# espnative-deadrail-2-g-rendered-poly-via.net
KiCad netlist of a schematic drawn in EAGLE
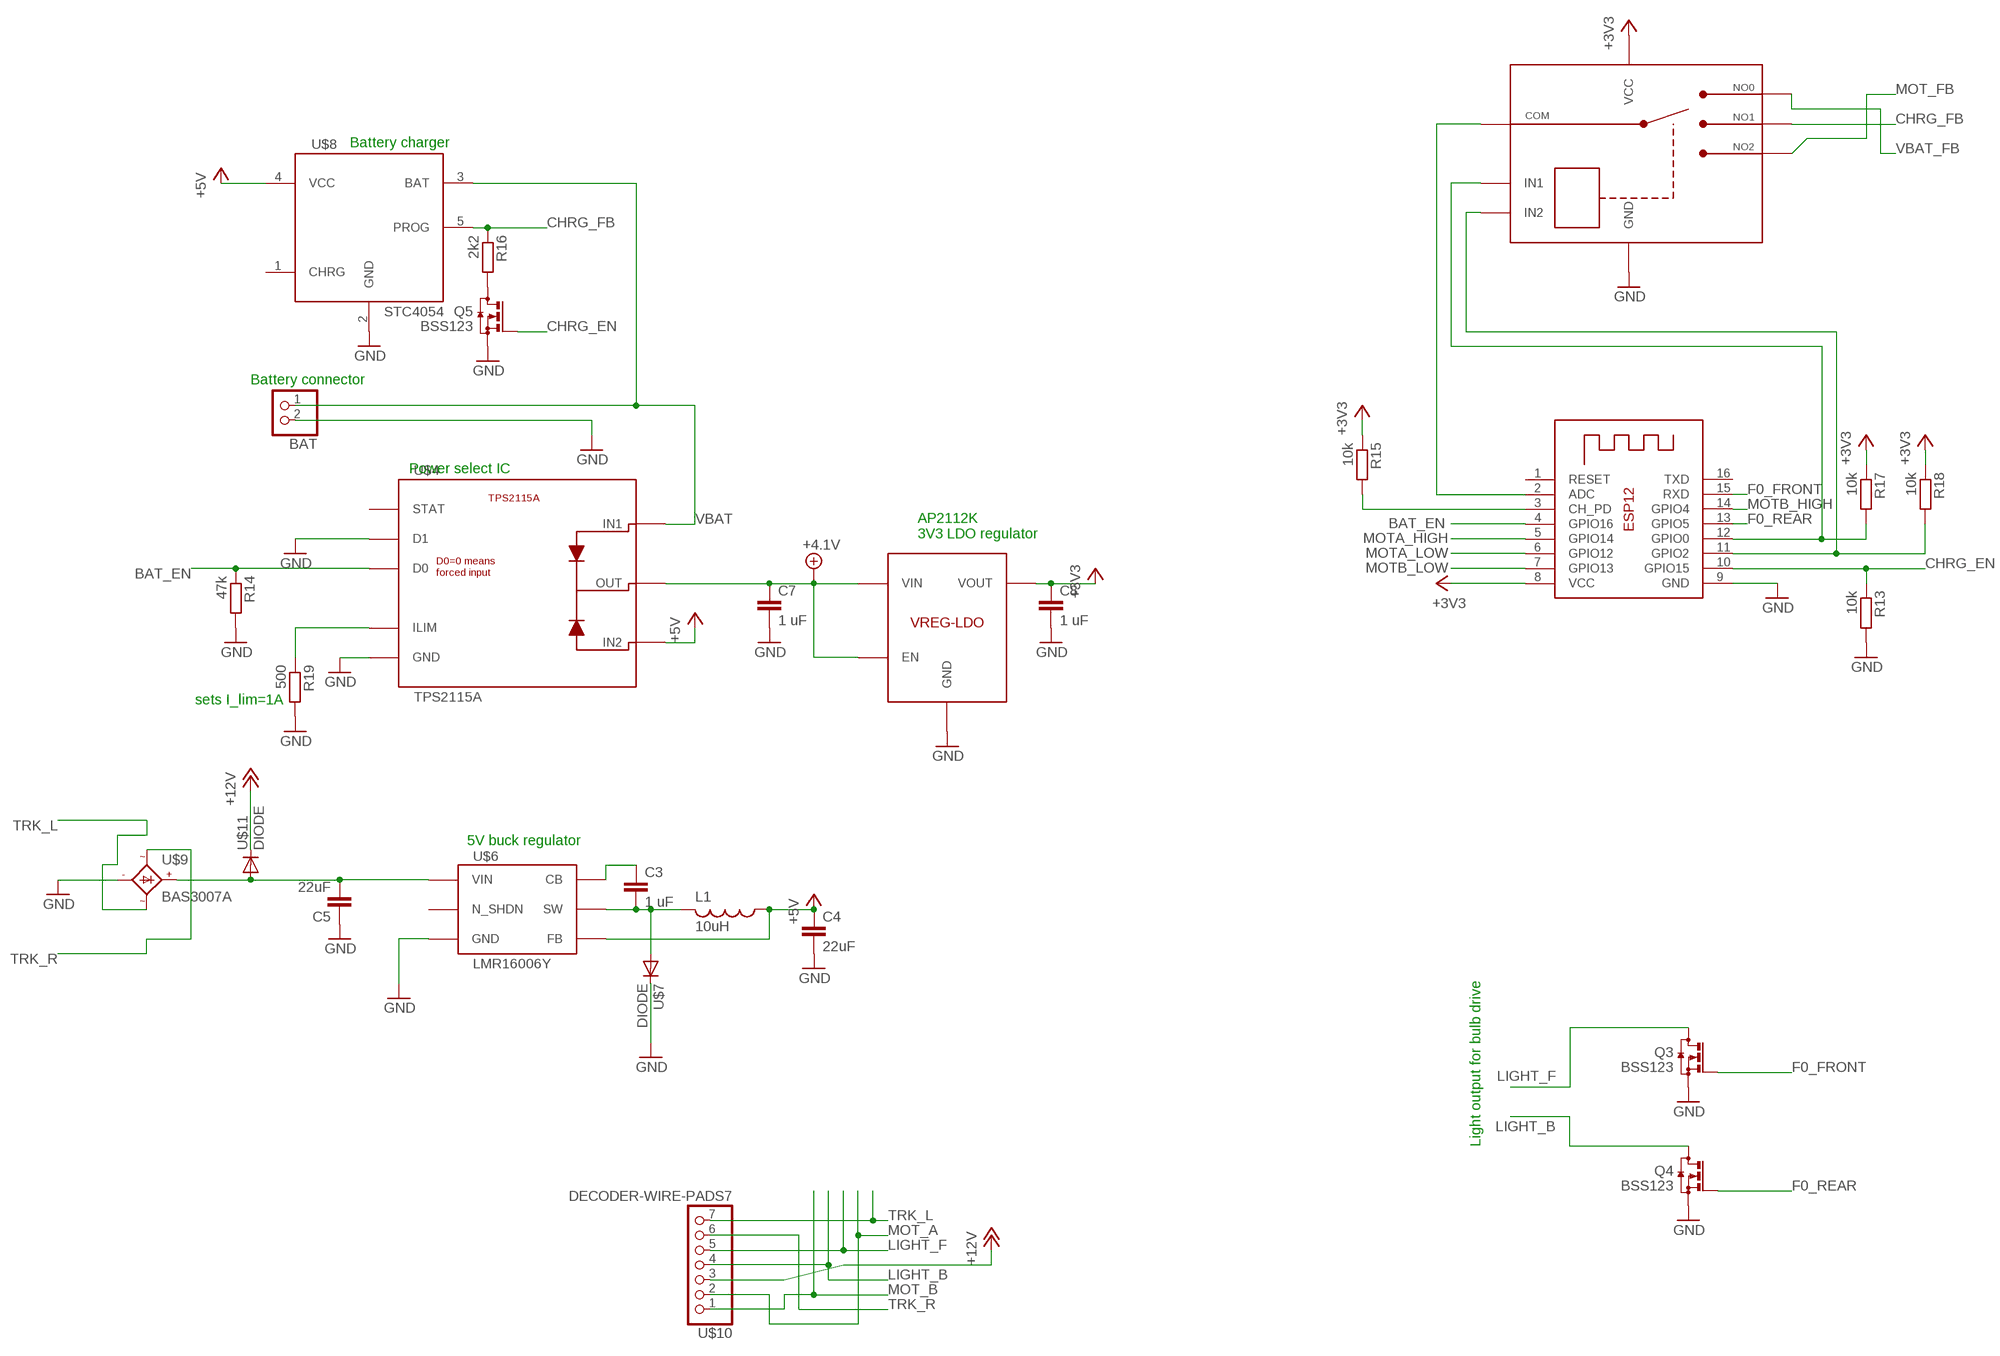
[diagram p0: schematic, sheet 1, part 1 of 2]
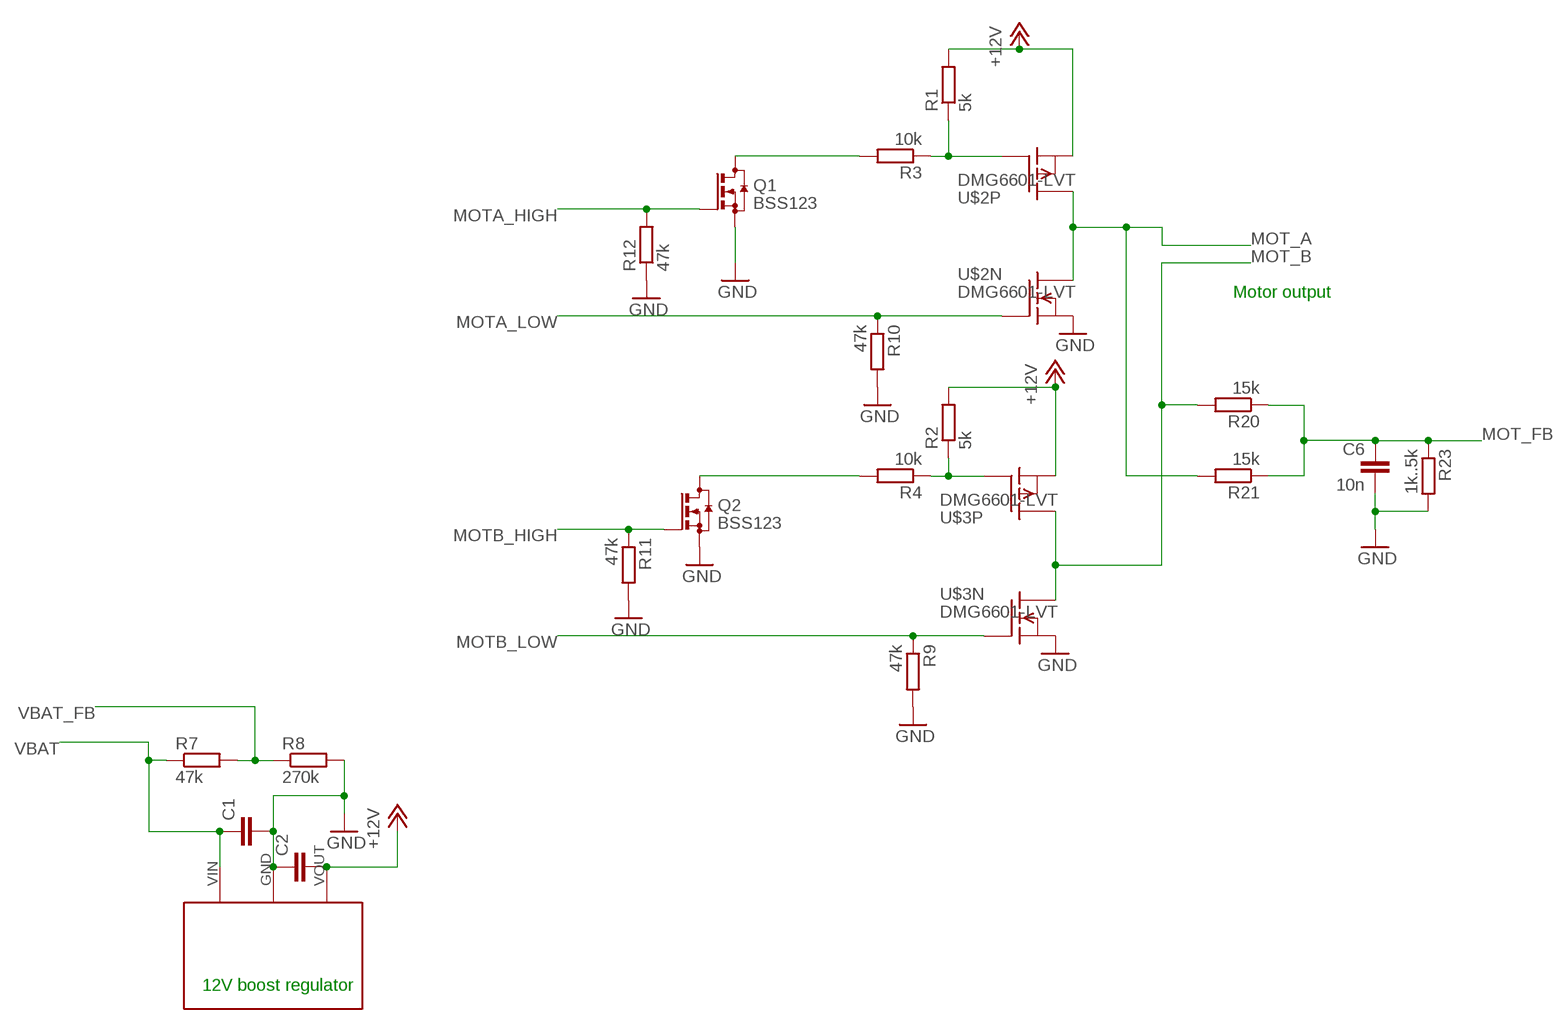
[diagram p1: schematic, sheet 1, part 2 of 2]

(export (version "E")
  (design (tool "Eeschema 10.0.6"))
  (components
    (comp (ref "BAT")
      (value "JST_2PIN-SMT-RA")
      (footprint "eagle-import:JST-PH-2-SMT-RA")
      (libsource (lib "eagle-import") (part "JST_2PIN-SMT-RA"))
    )
    (comp (ref "C1")
      (value "C-EUC1206")
      (footprint "eagle-import:C1206")
      (libsource (lib "eagle-import") (part "C-EUC1206"))
    )
    (comp (ref "C2")
      (value "C-EUC1206")
      (footprint "eagle-import:C1206")
      (libsource (lib "eagle-import") (part "C-EUC1206"))
    )
    (comp (ref "C3")
      (value "1 uF")
      (footprint "eagle-import:C0603")
      (libsource (lib "eagle-import") (part "C-EUC0603"))
    )
    (comp (ref "C4")
      (value "22uF")
      (footprint "eagle-import:C0603")
      (libsource (lib "eagle-import") (part "C-EUC0603"))
    )
    (comp (ref "C5")
      (value "22uF")
      (footprint "eagle-import:C1206")
      (libsource (lib "eagle-import") (part "C-EUC1206"))
    )
    (comp (ref "C6")
      (value "10n")
      (footprint "eagle-import:C0603")
      (libsource (lib "eagle-import") (part "C-EUC0603"))
    )
    (comp (ref "C7")
      (value "1 uF")
      (footprint "eagle-import:C0603")
      (libsource (lib "eagle-import") (part "C-EUC0603"))
    )
    (comp (ref "C8")
      (value "1 uF")
      (footprint "eagle-import:C0603")
      (libsource (lib "eagle-import") (part "C-EUC0603"))
    )
    (comp (ref "L1")
      (value "10uH")
      (footprint "eagle-import:FDSD0420")
      (libsource (lib "eagle-import") (part "FDSD0420"))
    )
    (comp (ref "Q1")
      (value "BSS123")
      (footprint "eagle-import:SOT23")
      (libsource (lib "eagle-import") (part "BSS123"))
    )
    (comp (ref "Q2")
      (value "BSS123")
      (footprint "eagle-import:SOT23")
      (libsource (lib "eagle-import") (part "BSS123"))
    )
    (comp (ref "Q3")
      (value "BSS123")
      (footprint "eagle-import:SOT23")
      (libsource (lib "eagle-import") (part "BSS123"))
    )
    (comp (ref "Q4")
      (value "BSS123")
      (footprint "eagle-import:SOT23")
      (libsource (lib "eagle-import") (part "BSS123"))
    )
    (comp (ref "Q5")
      (value "BSS123")
      (footprint "eagle-import:SOT23")
      (libsource (lib "eagle-import") (part "BSS123"))
    )
    (comp (ref "R1")
      (value "5k")
      (footprint "eagle-import:R0603")
      (libsource (lib "eagle-import") (part "R-EU_R0603"))
    )
    (comp (ref "R2")
      (value "5k")
      (footprint "eagle-import:R0603")
      (libsource (lib "eagle-import") (part "R-EU_R0603"))
    )
    (comp (ref "R3")
      (value "10k")
      (footprint "eagle-import:R0603")
      (libsource (lib "eagle-import") (part "R-EU_R0603"))
    )
    (comp (ref "R4")
      (value "10k")
      (footprint "eagle-import:R0603")
      (libsource (lib "eagle-import") (part "R-EU_R0603"))
    )
    (comp (ref "R7")
      (value "47k")
      (footprint "eagle-import:R0603")
      (libsource (lib "eagle-import") (part "R-EU_R0603"))
    )
    (comp (ref "R8")
      (value "270k")
      (footprint "eagle-import:R0603")
      (libsource (lib "eagle-import") (part "R-EU_R0603"))
    )
    (comp (ref "R9")
      (value "47k")
      (footprint "eagle-import:R0603")
      (libsource (lib "eagle-import") (part "R-EU_R0603"))
    )
    (comp (ref "R10")
      (value "47k")
      (footprint "eagle-import:R0603")
      (libsource (lib "eagle-import") (part "R-EU_R0603"))
    )
    (comp (ref "R11")
      (value "47k")
      (footprint "eagle-import:R0603")
      (libsource (lib "eagle-import") (part "R-EU_R0603"))
    )
    (comp (ref "R12")
      (value "47k")
      (footprint "eagle-import:R0603")
      (libsource (lib "eagle-import") (part "R-EU_R0603"))
    )
    (comp (ref "R13")
      (value "10k")
      (footprint "eagle-import:R0603")
      (libsource (lib "eagle-import") (part "R-EU_R0603"))
    )
    (comp (ref "R14")
      (value "47k")
      (footprint "eagle-import:R0603")
      (libsource (lib "eagle-import") (part "R-EU_R0603"))
    )
    (comp (ref "R15")
      (value "10k")
      (footprint "eagle-import:R0603")
      (libsource (lib "eagle-import") (part "R-EU_R0603"))
    )
    (comp (ref "R16")
      (value "2k2")
      (footprint "eagle-import:R0603")
      (libsource (lib "eagle-import") (part "R-EU_R0603"))
    )
    (comp (ref "R17")
      (value "10k")
      (footprint "eagle-import:R0603")
      (libsource (lib "eagle-import") (part "R-EU_R0603"))
    )
    (comp (ref "R18")
      (value "10k")
      (footprint "eagle-import:R0603")
      (libsource (lib "eagle-import") (part "R-EU_R0603"))
    )
    (comp (ref "R19")
      (value "500")
      (footprint "eagle-import:R0603")
      (libsource (lib "eagle-import") (part "R-EU_R0603"))
    )
    (comp (ref "R20")
      (value "15k")
      (footprint "eagle-import:R0603")
      (libsource (lib "eagle-import") (part "R-EU_R0603"))
    )
    (comp (ref "R21")
      (value "15k")
      (footprint "eagle-import:R0603")
      (libsource (lib "eagle-import") (part "R-EU_R0603"))
    )
    (comp (ref "R23")
      (value "1k..5k")
      (footprint "eagle-import:R0603")
      (libsource (lib "eagle-import") (part "R-EU_R0603"))
    )
    (comp (ref "U$1")
      (value "AP2112K-3V3")
      (footprint "eagle-import:SOT23-5L")
      (libsource (lib "eagle-import") (part "AP2112K"))
    )
    (comp (ref "U$2")
      (value "DMG6601-LVT")
      (footprint "eagle-import:TSOT-26")
      (libsource (lib "eagle-import") (part "DMG6601-LVT"))
    )
    (comp (ref "U$3")
      (value "DMG6601-LVT")
      (footprint "eagle-import:TSOT-26")
      (libsource (lib "eagle-import") (part "DMG6601-LVT"))
    )
    (comp (ref "U$4")
      (value "TPS2115A")
      (footprint "eagle-import:TSSOP-8")
      (libsource (lib "eagle-import") (part "TPS2115A"))
    )
    (comp (ref "U$5")
      (value "POLOLU-VREG12")
      (footprint "eagle-import:POLOLU-REGULATOR")
      (libsource (lib "eagle-import") (part "POLOLU-VREG12"))
    )
    (comp (ref "U$6")
      (value "LMR16006Y")
      (footprint "eagle-import:SOT23-6")
      (libsource (lib "eagle-import") (part "LMR16006Y"))
    )
    (comp (ref "U$7")
      (value "DIODE")
      (footprint "eagle-import:DIODE-1206")
      (libsource (lib "eagle-import") (part "DIODE"))
    )
    (comp (ref "U$8")
      (value "STC4054")
      (footprint "eagle-import:SOT23-5L")
      (libsource (lib "eagle-import") (part "STC4054"))
    )
    (comp (ref "U$9")
      (value "BAS3007A")
      (footprint "eagle-import:SOT143B")
      (libsource (lib "eagle-import") (part "BAS3007A"))
    )
    (comp (ref "U$10")
      (value "DECODER-WIRE-PADS7")
      (footprint "eagle-import:DECODER-WIRE-PADS")
      (libsource (lib "eagle-import") (part "DECODER-WIRE-PADS7"))
    )
    (comp (ref "U$11")
      (value "DIODE")
      (footprint "eagle-import:DIODE-1206")
      (libsource (lib "eagle-import") (part "DIODE"))
    )
    (comp (ref "U$12")
      (value "TS5A3359")
      (footprint "eagle-import:US8")
      (libsource (lib "eagle-import") (part "TS5A3359"))
    )
    (comp (ref "X1")
      (value "ESP-12")
      (footprint "eagle-import:ESP-12")
      (libsource (lib "eagle-import") (part "ESP-12"))
    )
  )
  (nets
    (net (code "1") (name "+3V3") (class "Default")
      (node (ref "C8") (pin "1") (pinfunction "1_1") (pintype "passive"))
      (node (ref "R15") (pin "1") (pinfunction "1_1") (pintype "passive"))
      (node (ref "R17") (pin "1") (pinfunction "1_1") (pintype "passive"))
      (node (ref "R18") (pin "1") (pinfunction "1_1") (pintype "passive"))
      (node (ref "U$1") (pin "5") (pinfunction "VOUT_5") (pintype "bidirectional"))
      (node (ref "U$12") (pin "8") (pinfunction "VCC_8") (pintype "bidirectional"))
      (node (ref "X1") (pin "8") (pinfunction "VCC_8") (pintype "power_in"))
    )
    (net (code "2") (name "+4.1V") (class "Default")
      (node (ref "C7") (pin "1") (pinfunction "1_1") (pintype "passive"))
      (node (ref "U$1") (pin "1") (pinfunction "VIN_1") (pintype "bidirectional"))
      (node (ref "U$1") (pin "3") (pinfunction "EN_3") (pintype "bidirectional"))
      (node (ref "U$4") (pin "7") (pinfunction "OUT_7") (pintype "bidirectional"))
    )
    (net (code "3") (name "+5V") (class "Default")
      (node (ref "C4") (pin "1") (pinfunction "1_1") (pintype "passive"))
      (node (ref "L1") (pin "P$1") (pinfunction "1_P$1") (pintype "passive"))
      (node (ref "U$4") (pin "6") (pinfunction "IN2_6") (pintype "bidirectional"))
      (node (ref "U$6") (pin "3") (pinfunction "FB_3") (pintype "bidirectional"))
      (node (ref "U$8") (pin "4") (pinfunction "VCC_4") (pintype "bidirectional"))
    )
    (net (code "4") (name "+12V") (class "Default")
      (node (ref "C2") (pin "2") (pinfunction "2_2") (pintype "passive"))
      (node (ref "R1") (pin "2") (pinfunction "2_2") (pintype "passive"))
      (node (ref "R2") (pin "2") (pinfunction "2_2") (pintype "passive"))
      (node (ref "U$10") (pin "3") (pinfunction "3_3") (pintype "passive"))
      (node (ref "U$11") (pin "C") (pinfunction "C_C") (pintype "passive"))
      (node (ref "U$2") (pin "2") (pinfunction "S_2") (pintype "passive"))
      (node (ref "U$3") (pin "2") (pinfunction "S_2") (pintype "passive"))
      (node (ref "U$5") (pin "VOUT") (pinfunction "VOUT_VOUT") (pintype "bidirectional"))
    )
    (net (code "5") (name "/BAT_EN") (class "Default")
      (node (ref "R14") (pin "1") (pinfunction "1_1") (pintype "passive"))
      (node (ref "U$4") (pin "2") (pinfunction "D0_2") (pintype "bidirectional"))
      (node (ref "X1") (pin "4") (pinfunction "GPIO16_4") (pintype "bidirectional"))
    )
    (net (code "6") (name "/CHRG_EN") (class "Default")
      (node (ref "Q5") (pin "1") (pinfunction "G_1") (pintype "passive"))
      (node (ref "R13") (pin "1") (pinfunction "1_1") (pintype "passive"))
      (node (ref "X1") (pin "10") (pinfunction "GPIO15_10") (pintype "bidirectional"))
    )
    (net (code "7") (name "/CHRG_FB") (class "Default")
      (node (ref "R16") (pin "1") (pinfunction "1_1") (pintype "passive"))
      (node (ref "U$12") (pin "2") (pinfunction "NO1_2") (pintype "bidirectional"))
      (node (ref "U$8") (pin "5") (pinfunction "PROG_5") (pintype "bidirectional"))
    )
    (net (code "8") (name "/F0_FRONT") (class "Default")
      (node (ref "Q3") (pin "1") (pinfunction "G_1") (pintype "passive"))
      (node (ref "X1") (pin "15") (pinfunction "RXD_15") (pintype "input"))
    )
    (net (code "9") (name "/F0_REAR") (class "Default")
      (node (ref "Q4") (pin "1") (pinfunction "G_1") (pintype "passive"))
      (node (ref "X1") (pin "13") (pinfunction "GPIO5_13") (pintype "bidirectional"))
    )
    (net (code "10") (name "/LIGHT_B") (class "Default")
      (node (ref "Q4") (pin "3") (pinfunction "D_3") (pintype "passive"))
      (node (ref "U$10") (pin "4") (pinfunction "4_4") (pintype "passive"))
    )
    (net (code "11") (name "/LIGHT_F") (class "Default")
      (node (ref "Q3") (pin "3") (pinfunction "D_3") (pintype "passive"))
      (node (ref "U$10") (pin "5") (pinfunction "5_5") (pintype "passive"))
    )
    (net (code "12") (name "/MOTA_HIGH") (class "Default")
      (node (ref "Q1") (pin "1") (pinfunction "G_1") (pintype "passive"))
      (node (ref "R12") (pin "2") (pinfunction "2_2") (pintype "passive"))
      (node (ref "X1") (pin "5") (pinfunction "GPIO14_5") (pintype "bidirectional"))
    )
    (net (code "13") (name "/MOTA_LOW") (class "Default")
      (node (ref "R10") (pin "1") (pinfunction "1_1") (pintype "passive"))
      (node (ref "U$2") (pin "1") (pinfunction "G_1") (pintype "passive"))
      (node (ref "X1") (pin "6") (pinfunction "GPIO12_6") (pintype "bidirectional"))
    )
    (net (code "14") (name "/MOTB_HIGH") (class "Default")
      (node (ref "Q2") (pin "1") (pinfunction "G_1") (pintype "passive"))
      (node (ref "R11") (pin "1") (pinfunction "1_1") (pintype "passive"))
      (node (ref "X1") (pin "14") (pinfunction "GPIO4_14") (pintype "bidirectional"))
    )
    (net (code "15") (name "/MOTB_LOW") (class "Default")
      (node (ref "R9") (pin "1") (pinfunction "1_1") (pintype "passive"))
      (node (ref "U$3") (pin "1") (pinfunction "G_1") (pintype "passive"))
      (node (ref "X1") (pin "7") (pinfunction "GPIO13_7") (pintype "bidirectional"))
    )
    (net (code "16") (name "/MOT_A") (class "Default")
      (node (ref "R21") (pin "2") (pinfunction "2_2") (pintype "passive"))
      (node (ref "U$10") (pin "2") (pinfunction "2_2") (pintype "passive"))
      (node (ref "U$2") (pin "4") (pinfunction "D_4") (pintype "passive"))
      (node (ref "U$2") (pin "6") (pinfunction "D_6") (pintype "passive"))
    )
    (net (code "17") (name "/MOT_B") (class "Default")
      (node (ref "R20") (pin "2") (pinfunction "2_2") (pintype "passive"))
      (node (ref "U$10") (pin "1") (pinfunction "1_1") (pintype "passive"))
      (node (ref "U$3") (pin "4") (pinfunction "D_4") (pintype "passive"))
      (node (ref "U$3") (pin "6") (pinfunction "D_6") (pintype "passive"))
    )
    (net (code "18") (name "/MOT_FB") (class "Default")
      (node (ref "C6") (pin "1") (pinfunction "1_1") (pintype "passive"))
      (node (ref "R20") (pin "1") (pinfunction "1_1") (pintype "passive"))
      (node (ref "R21") (pin "1") (pinfunction "1_1") (pintype "passive"))
      (node (ref "R23") (pin "1") (pinfunction "1_1") (pintype "passive"))
      (node (ref "U$12") (pin "3") (pinfunction "NO2_3") (pintype "bidirectional"))
    )
    (net (code "19") (name "/TRK_L") (class "Default")
      (node (ref "U$10") (pin "7") (pinfunction "7_7") (pintype "passive"))
      (node (ref "U$9") (pin "3") (pinfunction "AC2_3") (pintype "passive"))
    )
    (net (code "20") (name "/TRK_R") (class "Default")
      (node (ref "U$10") (pin "6") (pinfunction "6_6") (pintype "passive"))
      (node (ref "U$9") (pin "2") (pinfunction "AC1_2") (pintype "passive"))
    )
    (net (code "21") (name "/VBAT") (class "Default")
      (node (ref "BAT") (pin "1") (pinfunction "2_1") (pintype "passive"))
      (node (ref "C1") (pin "1") (pinfunction "1_1") (pintype "passive"))
      (node (ref "R7") (pin "1") (pinfunction "1_1") (pintype "passive"))
      (node (ref "U$4") (pin "8") (pinfunction "IN1_8") (pintype "bidirectional"))
      (node (ref "U$5") (pin "VIN") (pinfunction "VIN_VIN") (pintype "bidirectional"))
      (node (ref "U$8") (pin "3") (pinfunction "BAT_3") (pintype "bidirectional"))
    )
    (net (code "22") (name "/VBAT_FB") (class "Default")
      (node (ref "R7") (pin "2") (pinfunction "2_2") (pintype "passive"))
      (node (ref "R8") (pin "1") (pinfunction "1_1") (pintype "passive"))
      (node (ref "U$12") (pin "1") (pinfunction "NO0_1") (pintype "bidirectional"))
    )
    (net (code "23") (name "GND") (class "Default")
      (node (ref "BAT") (pin "2") (pinfunction "1_2") (pintype "passive"))
      (node (ref "C1") (pin "2") (pinfunction "2_2") (pintype "passive"))
      (node (ref "C2") (pin "1") (pinfunction "1_1") (pintype "passive"))
      (node (ref "C4") (pin "2") (pinfunction "2_2") (pintype "passive"))
      (node (ref "C5") (pin "1") (pinfunction "1_1") (pintype "passive"))
      (node (ref "C6") (pin "2") (pinfunction "2_2") (pintype "passive"))
      (node (ref "C7") (pin "2") (pinfunction "2_2") (pintype "passive"))
      (node (ref "C8") (pin "2") (pinfunction "2_2") (pintype "passive"))
      (node (ref "Q1") (pin "2") (pinfunction "S_2") (pintype "passive"))
      (node (ref "Q2") (pin "2") (pinfunction "S_2") (pintype "passive"))
      (node (ref "Q3") (pin "2") (pinfunction "S_2") (pintype "passive"))
      (node (ref "Q4") (pin "2") (pinfunction "S_2") (pintype "passive"))
      (node (ref "Q5") (pin "2") (pinfunction "S_2") (pintype "passive"))
      (node (ref "R10") (pin "2") (pinfunction "2_2") (pintype "passive"))
      (node (ref "R11") (pin "2") (pinfunction "2_2") (pintype "passive"))
      (node (ref "R12") (pin "1") (pinfunction "1_1") (pintype "passive"))
      (node (ref "R13") (pin "2") (pinfunction "2_2") (pintype "passive"))
      (node (ref "R14") (pin "2") (pinfunction "2_2") (pintype "passive"))
      (node (ref "R19") (pin "2") (pinfunction "2_2") (pintype "passive"))
      (node (ref "R23") (pin "2") (pinfunction "2_2") (pintype "passive"))
      (node (ref "R8") (pin "2") (pinfunction "2_2") (pintype "passive"))
      (node (ref "R9") (pin "2") (pinfunction "2_2") (pintype "passive"))
      (node (ref "U$1") (pin "2") (pinfunction "GND_2") (pintype "bidirectional"))
      (node (ref "U$12") (pin "4") (pinfunction "GND_4") (pintype "bidirectional"))
      (node (ref "U$2") (pin "5") (pinfunction "S_5") (pintype "passive"))
      (node (ref "U$3") (pin "5") (pinfunction "S_5") (pintype "passive"))
      (node (ref "U$4") (pin "3") (pinfunction "D1_3") (pintype "bidirectional"))
      (node (ref "U$4") (pin "5") (pinfunction "GND_5") (pintype "bidirectional"))
      (node (ref "U$5") (pin "GND") (pinfunction "GND_GND") (pintype "bidirectional"))
      (node (ref "U$6") (pin "2") (pinfunction "GND_2") (pintype "bidirectional"))
      (node (ref "U$7") (pin "C") (pinfunction "C_C") (pintype "passive"))
      (node (ref "U$8") (pin "2") (pinfunction "GND_2") (pintype "bidirectional"))
      (node (ref "U$9") (pin "1") (pinfunction "-_1") (pintype "passive"))
      (node (ref "X1") (pin "9") (pinfunction "GND_9") (pintype "power_in"))
    )
    (net (code "24") (name "Net-(L1-2)") (class "Default")
      (node (ref "C3") (pin "2") (pinfunction "2_2") (pintype "passive"))
      (node (ref "L1") (pin "P$2") (pinfunction "2_P$2") (pintype "passive"))
      (node (ref "U$6") (pin "6") (pinfunction "SW_6") (pintype "bidirectional"))
      (node (ref "U$7") (pin "A") (pinfunction "A_A") (pintype "passive"))
    )
    (net (code "25") (name "Net-(Q1-D)") (class "Default")
      (node (ref "Q1") (pin "3") (pinfunction "D_3") (pintype "passive"))
      (node (ref "R3") (pin "2") (pinfunction "2_2") (pintype "passive"))
    )
    (net (code "26") (name "Net-(Q2-D)") (class "Default")
      (node (ref "Q2") (pin "3") (pinfunction "D_3") (pintype "passive"))
      (node (ref "R4") (pin "2") (pinfunction "2_2") (pintype "passive"))
    )
    (net (code "27") (name "Net-(Q5-D)") (class "Default")
      (node (ref "Q5") (pin "3") (pinfunction "D_3") (pintype "passive"))
      (node (ref "R16") (pin "2") (pinfunction "2_2") (pintype "passive"))
    )
    (net (code "28") (name "Net-(U$2B-G)") (class "Default")
      (node (ref "R1") (pin "1") (pinfunction "1_1") (pintype "passive"))
      (node (ref "R3") (pin "1") (pinfunction "1_1") (pintype "passive"))
      (node (ref "U$2") (pin "3") (pinfunction "G_3") (pintype "passive"))
    )
    (net (code "29") (name "Net-(U$3B-G)") (class "Default")
      (node (ref "R2") (pin "1") (pinfunction "1_1") (pintype "passive"))
      (node (ref "R4") (pin "1") (pinfunction "1_1") (pintype "passive"))
      (node (ref "U$3") (pin "3") (pinfunction "G_3") (pintype "passive"))
    )
    (net (code "30") (name "Net-(U$4-ILIM)") (class "Default")
      (node (ref "R19") (pin "1") (pinfunction "1_1") (pintype "passive"))
      (node (ref "U$4") (pin "4") (pinfunction "ILIM_4") (pintype "bidirectional"))
    )
    (net (code "31") (name "Net-(U$6-CB)") (class "Default")
      (node (ref "C3") (pin "1") (pinfunction "1_1") (pintype "passive"))
      (node (ref "U$6") (pin "1") (pinfunction "CB_1") (pintype "bidirectional"))
    )
    (net (code "32") (name "Net-(U$6-VIN)") (class "Default")
      (node (ref "C5") (pin "2") (pinfunction "2_2") (pintype "passive"))
      (node (ref "U$11") (pin "A") (pinfunction "A_A") (pintype "passive"))
      (node (ref "U$6") (pin "5") (pinfunction "VIN_5") (pintype "bidirectional"))
      (node (ref "U$9") (pin "4") (pinfunction "+_4") (pintype "passive"))
    )
    (net (code "33") (name "Net-(U$12-COM)") (class "Default")
      (node (ref "U$12") (pin "7") (pinfunction "COM_7") (pintype "bidirectional"))
      (node (ref "X1") (pin "2") (pinfunction "ADC_2") (pintype "passive"))
    )
    (net (code "34") (name "Net-(U$12-IN1)") (class "Default")
      (node (ref "R17") (pin "2") (pinfunction "2_2") (pintype "passive"))
      (node (ref "U$12") (pin "6") (pinfunction "IN1_6") (pintype "bidirectional"))
      (node (ref "X1") (pin "12") (pinfunction "GPIO0_12") (pintype "bidirectional"))
    )
    (net (code "35") (name "Net-(U$12-IN2)") (class "Default")
      (node (ref "R18") (pin "2") (pinfunction "2_2") (pintype "passive"))
      (node (ref "U$12") (pin "5") (pinfunction "IN2_5") (pintype "bidirectional"))
      (node (ref "X1") (pin "11") (pinfunction "GPIO2_11") (pintype "bidirectional"))
    )
    (net (code "36") (name "Net-(X1-CH_PD)") (class "Default")
      (node (ref "R15") (pin "2") (pinfunction "2_2") (pintype "passive"))
      (node (ref "X1") (pin "3") (pinfunction "CH_PD_3") (pintype "input"))
    )
    (net (code "37") (name "unconnected-(U$4-STAT-Pad1)") (class "Default")
      (node (ref "U$4") (pin "1") (pinfunction "STAT_1") (pintype "bidirectional"))
    )
    (net (code "38") (name "unconnected-(U$6-N_SHDN-Pad4)") (class "Default")
      (node (ref "U$6") (pin "4") (pinfunction "N_SHDN_4") (pintype "bidirectional"))
    )
    (net (code "39") (name "unconnected-(U$8-CHRG-Pad1)") (class "Default")
      (node (ref "U$8") (pin "1") (pinfunction "CHRG_1") (pintype "bidirectional"))
    )
    (net (code "40") (name "unconnected-(X1-RESET-Pad1)") (class "Default")
      (node (ref "X1") (pin "1") (pinfunction "RESET_1") (pintype "input"))
    )
    (net (code "41") (name "unconnected-(X1-TXD-Pad16)") (class "Default")
      (node (ref "X1") (pin "16") (pinfunction "TXD_16") (pintype "output"))
    )
  )
)
